# DC_DC_ISO.net
KiCad netlist of a schematic drawn in Altium Designer
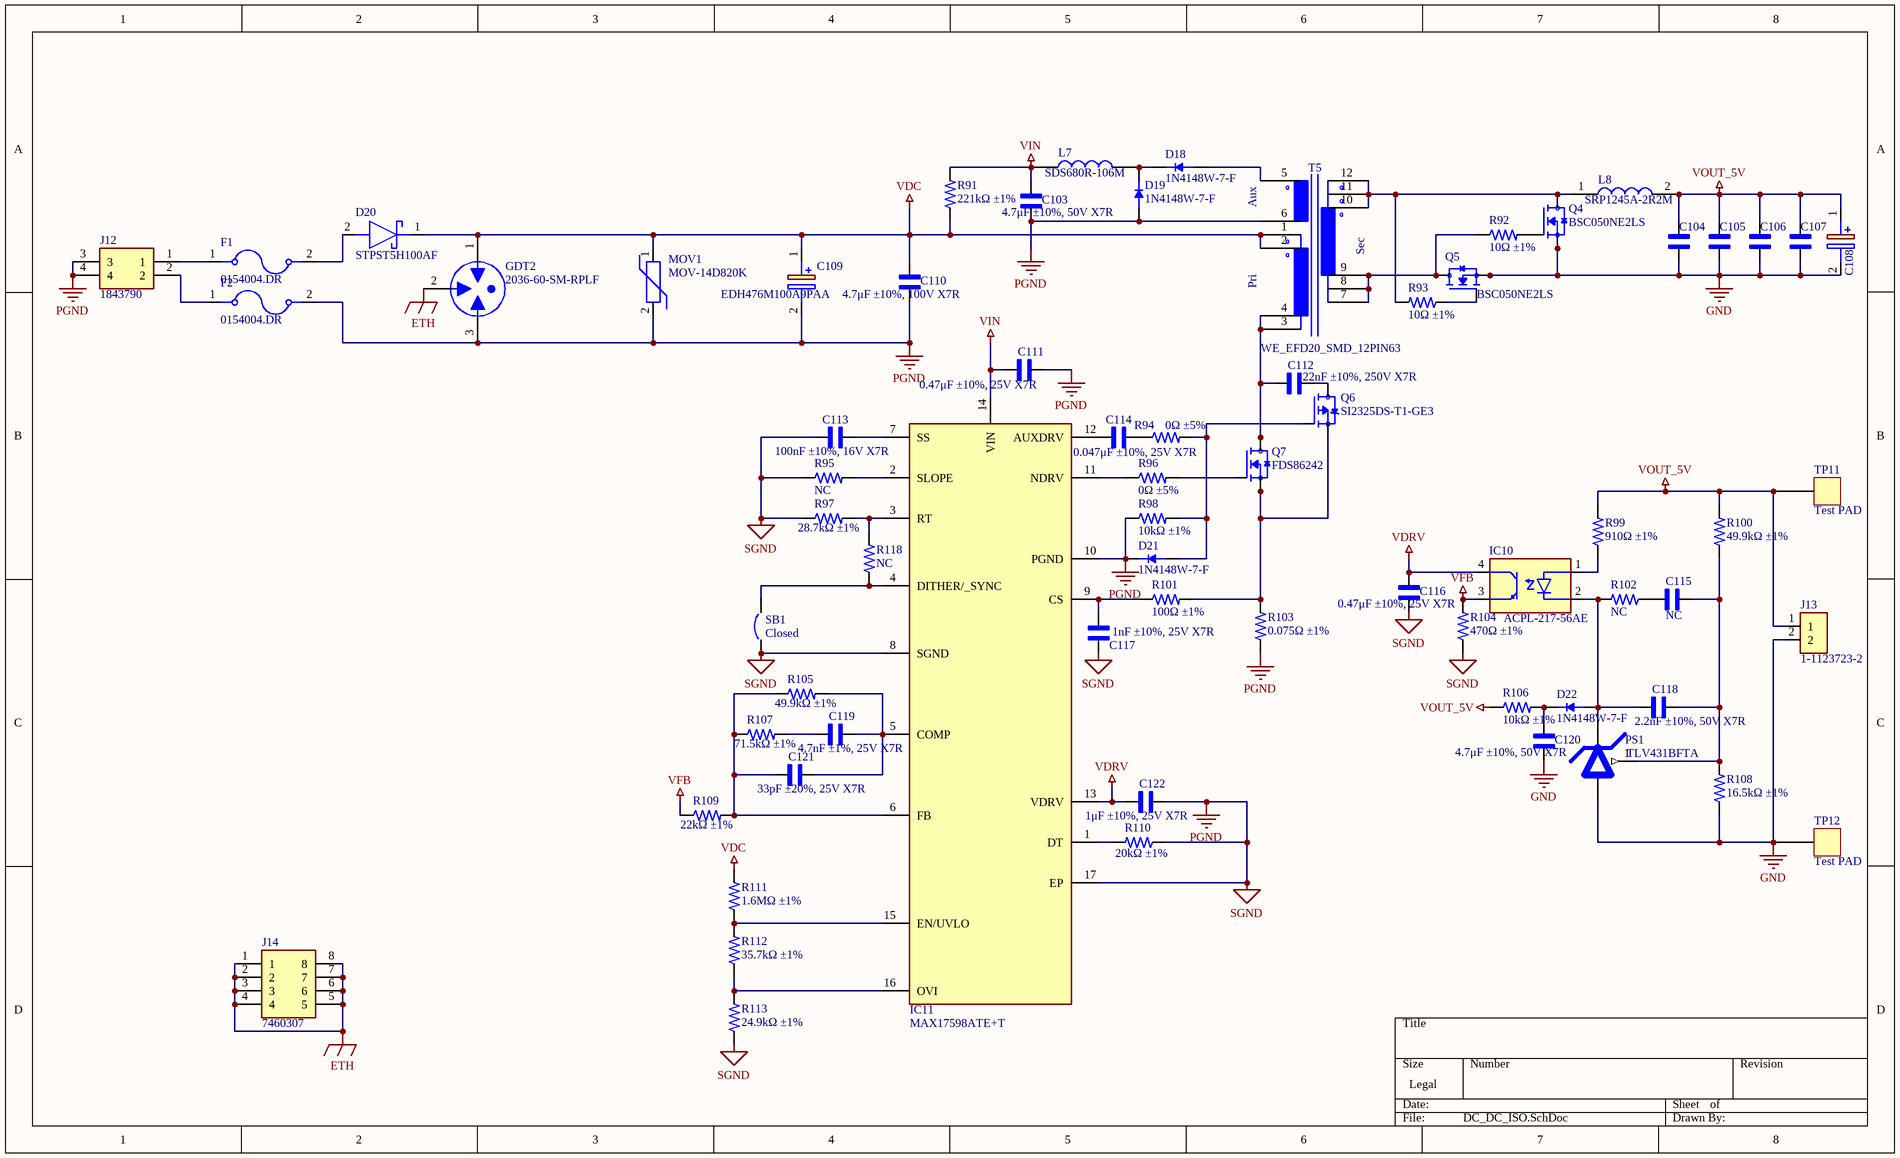
[diagram p0: DC_DC_ISO.SchDoc]

(export (version "E")
  (design (tool "Eeschema 10.0.6"))
  (components
    (comp (ref "C103")
      (value "4.7μF ±10%, 50V X7R")
      (footprint "1206_C")
      (fields (field (name "MP") "LD03ZD475MAB2A"))
      (libsource (lib "DC_DC") (part "CAP"))
    )
    (comp (ref "C104")
      (value "47μF ±10%, 10V X7R")
      (footprint "1210_C")
      (description "Capacitor non polar")
      (fields (field (name "MP") "LD03ZD475MAB2A"))
      (libsource (lib "DC_DC") (part "CAP"))
    )
    (comp (ref "C105")
      (value "47μF ±10%, 10V X7R")
      (footprint "1210_C")
      (description "Capacitor non polar")
      (fields (field (name "MP") "LD03ZD475MAB2A"))
      (libsource (lib "DC_DC") (part "CAP"))
    )
    (comp (ref "C106")
      (value "47μF ±10%, 10V X7R")
      (footprint "1210_C")
      (description "Capacitor non polar")
      (fields (field (name "MP") "LD03ZD475MAB2A"))
      (libsource (lib "DC_DC") (part "CAP"))
    )
    (comp (ref "C107")
      (value "47μF ±10%, 10V X7R")
      (footprint "1210_C")
      (description "Capacitor non polar")
      (fields (field (name "MP") "LD03ZD475MAB2A"))
      (libsource (lib "DC_DC") (part "CAP"))
    )
    (comp (ref "C108")
      (value "TCJ5477M016R0100E/NI")
      (footprint "SamacSys:CAPPM7344X400N")
      (description "Capacitor Polarised")
      (fields
        (field (name "MANUFACTURER_PART_NUMBER") "TCJ5477M016R0100E")
        (field (name "MOUSER PART NUMBER") "581-TCJ5477M016R100E")
      )
      (libsource (lib "*") (part "TCJ5477M016R0100E"))
    )
    (comp (ref "C109")
      (value "EDH476M100A9PAA")
      (footprint "SamacSys:CAPAE1030X1050N")
      (description "Capacitor Polarised")
      (fields (field (name "MOUSER PART NUMBER") "80-EDH476M100A9PAA"))
      (libsource (lib "*") (part "EDH476M100A9PAA"))
    )
    (comp (ref "C110")
      (value "4.7μF ±10%, 100V X7R")
      (footprint "1210_C")
      (fields (field (name "MP") "LD03ZD475MAB2A"))
      (libsource (lib "DC_DC") (part "CAP"))
    )
    (comp (ref "C111")
      (value "0.47μF ±10%, 25V X7R")
      (footprint "0603_C")
      (fields (field (name "MP") "LD03ZD475MAB2A"))
      (libsource (lib "") (part "CAP_1"))
    )
    (comp (ref "C112")
      (value "22nF ±10%, 250V X7R")
      (footprint "0805_C")
      (fields (field (name "MP") "LD03ZD475MAB2A"))
      (libsource (lib "") (part "CAP_2"))
    )
    (comp (ref "C113")
      (value "100nF ±10%, 16V X7R")
      (footprint "0603_C")
      (fields (field (name "MP") "LD03ZD475MAB2A"))
      (libsource (lib "") (part "CAP_1"))
    )
    (comp (ref "C114")
      (value "0.047μF ±10%, 25V X7R")
      (footprint "0603_C")
      (fields (field (name "MP") "LD03ZD475MAB2A"))
      (libsource (lib "") (part "CAP_2"))
    )
    (comp (ref "C115")
      (value "NC")
      (footprint "0603_C")
      (fields (field (name "MP") "LD03ZD475MAB2A"))
      (libsource (lib "") (part "CAP_2"))
    )
    (comp (ref "C116")
      (value "0.47μF ±10%, 25V X7R")
      (footprint "0603_C")
      (fields (field (name "MP") "LD03ZD475MAB2A"))
      (libsource (lib "DC_DC") (part "CAP"))
    )
    (comp (ref "C117")
      (value "1nF ±10%, 25V X7R")
      (footprint "0603_C")
      (fields (field (name "MP") "LD03ZD475MAB2A"))
      (libsource (lib "DC_DC") (part "CAP"))
    )
    (comp (ref "C118")
      (value "2.2nF ±10%, 50V X7R")
      (footprint "0603_C")
      (fields (field (name "MP") "LD03ZD475MAB2A"))
      (libsource (lib "") (part "CAP_2"))
    )
    (comp (ref "C119")
      (value "4.7nF ±1%, 25V X7R")
      (footprint "0603_C")
      (fields (field (name "MP") "LD03ZD475MAB2A"))
      (libsource (lib "") (part "CAP_1"))
    )
    (comp (ref "C120")
      (value "4.7μF ±10%, 50V X7R")
      (footprint "1206_C")
      (fields (field (name "MP") "LD03ZD475MAB2A"))
      (libsource (lib "DC_DC") (part "CAP"))
    )
    (comp (ref "C121")
      (value "33pF ±20%, 25V X7R")
      (footprint "0603_C")
      (fields (field (name "MP") "LD03ZD475MAB2A"))
      (libsource (lib "") (part "CAP_1"))
    )
    (comp (ref "C122")
      (value "1μF ±10%, 25V X7R")
      (footprint "0805_C")
      (fields (field (name "MP") "LD03ZD475MAB2A"))
      (libsource (lib "") (part "CAP_1"))
    )
    (comp (ref "D18")
      (value "1N4148W-7-F")
      (footprint "SOD3715X135N")
      (description "Diode Standard 100 V 300mA (DC) Surface Mount SOD-123")
      (fields (field (name "MF") "Diodes Inc."))
      (libsource (lib "DC_DC") (part "1N4148W-7-F"))
    )
    (comp (ref "D19")
      (value "1N4148W-7-F")
      (footprint "SOD3715X135N")
      (description "Diode Standard 100 V 300mA (DC) Surface Mount SOD-123")
      (fields (field (name "MF") "Diodes Inc."))
      (libsource (lib "DC_DC") (part "1N4148W-7-F"))
    )
    (comp (ref "D20")
      (value "STPST5H100AF")
      (footprint "SODFL4724X103N")
      (description "Schottky Diode")
      (fields (field (name "MOUSER PART NUMBER") "511-STPST5H100AF"))
      (libsource (lib "DC_DC") (part "STPST5H100AF"))
    )
    (comp (ref "D21")
      (value "1N4148W-7-F")
      (footprint "SOD3715X135N")
      (description "Diode Standard 100 V 300mA (DC) Surface Mount SOD-123")
      (fields (field (name "MF") "Diodes Inc."))
      (libsource (lib "DC_DC") (part "1N4148W-7-F"))
    )
    (comp (ref "D22")
      (value "1N4148W-7-F")
      (footprint "SOD3715X135N")
      (description "Diode Standard 100 V 300mA (DC) Surface Mount SOD-123")
      (fields (field (name "MF") "Diodes Inc."))
      (libsource (lib "DC_DC") (part "1N4148W-7-F"))
    )
    (comp (ref "F1")
      (value "0154004.DR")
      (footprint "FUSE_0154004.DR")
      (description "154/154T/154L/154TL Series OMNI-BLOKÂ® Fuse and Holder Assembly")
      (libsource (lib "DC_DC") (part "0154004.DR"))
    )
    (comp (ref "F2")
      (value "0154004.DR")
      (footprint "FUSE_0154004.DR")
      (description "154/154T/154L/154TL Series OMNI-BLOKÂ® Fuse and Holder Assembly")
      (libsource (lib "DC_DC") (part "0154004.DR"))
    )
    (comp (ref "GDT2")
      (value "2036-60-SM-RPLF")
      (footprint "2036-60-SM-RPLF")
      (description "Gas Discharge Tubes - GDTs / Gas Plasma Arrestors Sparkover100V/s 600V Miniature 3 Pole")
      (libsource (lib "DC_DC") (part "2036-60-SM-RPLF"))
    )
    (comp (ref "IC10")
      (value "ACPL-217-56AE")
      (footprint "SOIC127P700X242-4N")
      (description "Integrated Circuit")
      (fields (field (name "MOUSER PART NUMBER") "630-ACPL-217-56AE"))
      (libsource (lib "DC_DC") (part "ACPL-217-56AE"))
    )
    (comp (ref "IC11")
      (value "MAX17598ATE+T")
      (footprint "QFN50P300X300X80-17N")
      (description "Integrated Circuit")
      (fields (field (name "MOUSER PART NUMBER") "700-MAX17598ATE+T"))
      (libsource (lib "DC_DC") (part "MAX17598ATE+T"))
    )
    (comp (ref "J12")
      (value "1843790")
      (footprint "SamacSys:1843790")
      (description "Connector")
      (fields (field (name "MOUSER PART NUMBER") "651-1843790"))
      (libsource (lib "*") (part "1843790"))
    )
    (comp (ref "J13")
      (value "1-1123723-2")
      (footprint "TE_1-1123723-2")
      (description "3.96 EP HDR ASSY 2P_NATURAL_")
      (fields (field (name "MF") "TE Connectivity") (field (name "DIGI-KEY_PART_NUMBER") "A111830-ND"))
      (libsource (lib "1-1123723-2") (part "1-1123723-2"))
    )
    (comp (ref "J14")
      (value "7460307")
      (footprint "7460307")
      (description "Connector")
      (fields (field (name "MOUSER PART NUMBER") "710-7460307"))
      (libsource (lib "DC_DC") (part "7460307"))
    )
    (comp (ref "L7")
      (value "SDS680R-106M")
      (footprint "SRR6603332ML")
      (description "Inductor 10mH")
      (fields
        (field (name "MANUFACTURER_PART_NUMBER") "SRR6603-103ML")
        (field (name "MOUSER PART NUMBER") "652-SRR6603-103ML")
      )
      (libsource (lib "DC_DC") (part "SDS680R-106M"))
    )
    (comp (ref "L8")
      (value "SRP1245A-2R2M")
      (footprint "INDPM135125X500N")
      (description "Inductor 2.2uH")
      (fields (field (name "MOUSER PART NUMBER") "652-SRP1245A-2R2M"))
      (libsource (lib "DC_DC") (part "SRP1245A-2R2M"))
    )
    (comp (ref "MOV1")
      (value "MOV-14D820K")
      (footprint "MOV-14D820K")
      (description "Varistors 82volts 14mm")
      (fields (field (name "MP") "MOV-14D471K") (field (name "MF") "Bourns"))
      (libsource (lib "DC_DC") (part "MOV-14D820K"))
    )
    (comp (ref "PS1")
      (value "TLV431BFTA")
      (footprint "SOT96P240X100-3N")
      (description "Power Supply")
      (fields (field (name "MOUSER PART NUMBER") "621-TLV431BFTA"))
      (libsource (lib "DC_DC") (part "TLV431BFTA"))
    )
    (comp (ref "Q4")
      (value "BSC050NE2LS")
      (footprint "BSC050NE2LS")
      (description "MOSFET (N-Channel)")
      (fields (field (name "MOUSER PART NUMBER") "726-BSC050NE2LS"))
      (libsource (lib "DC_DC") (part "BSC050NE2LS"))
    )
    (comp (ref "Q5")
      (value "BSC050NE2LS")
      (footprint "BSC050NE2LS")
      (description "MOSFET (N-Channel)")
      (fields (field (name "MOUSER PART NUMBER") "726-BSC050NE2LS"))
      (libsource (lib "DC_DC") (part "BSC050NE2LS"))
    )
    (comp (ref "Q6")
      (value "SI2325DS-T1-GE3")
      (footprint "SOT-23")
      (description "150V 0.69A 1.25W 1.2ohm at 10V")
      (fields (field (name "MF") "Vishay Siliconix"))
      (libsource (lib "DC_DC") (part "SI2325DS-T1-GE3"))
    )
    (comp (ref "Q7")
      (value "FDS86242")
      (footprint "SOIC127P600X175-8N")
      (description "Integrated Circuit")
      (fields (field (name "MOUSER PART NUMBER") "512-FDS86242"))
      (libsource (lib "DC_DC") (part "FDS86242"))
    )
    (comp (ref "R91")
      (value "221kΩ ±1%")
      (footprint "0805_R")
      (fields (field (name "MP") "3-1879460-6"))
      (libsource (lib "DC_DC") (part "RES"))
    )
    (comp (ref "R92")
      (value "10Ω ±1%")
      (footprint "0603_R")
      (fields (field (name "MP") "3-1879460-6"))
      (libsource (lib "DC_DC") (part "RES"))
    )
    (comp (ref "R93")
      (value "10Ω ±1%")
      (footprint "0603_R")
      (fields (field (name "MP") "3-1879460-6"))
      (libsource (lib "DC_DC") (part "RES"))
    )
    (comp (ref "R94")
      (value "0Ω ±5%")
      (footprint "0603_R")
      (fields (field (name "MP") "3-1879460-6"))
      (libsource (lib "DC_DC") (part "RES"))
    )
    (comp (ref "R95")
      (value "NC")
      (footprint "0603_R")
      (fields (field (name "MP") "3-1879460-6"))
      (libsource (lib "DC_DC") (part "RES"))
    )
    (comp (ref "R96")
      (value "0Ω ±5%")
      (footprint "0603_R")
      (fields (field (name "MP") "3-1879460-6"))
      (libsource (lib "DC_DC") (part "RES"))
    )
    (comp (ref "R97")
      (value "28.7kΩ ±1%")
      (footprint "0603_R")
      (fields (field (name "MP") "3-1879460-6"))
      (libsource (lib "DC_DC") (part "RES"))
    )
    (comp (ref "R98")
      (value "10kΩ ±1%")
      (footprint "0603_R")
      (fields (field (name "MP") "3-1879460-6"))
      (libsource (lib "DC_DC") (part "RES"))
    )
    (comp (ref "R99")
      (value "910Ω ±1%")
      (footprint "0603_R")
      (fields (field (name "MP") "3-1879460-6"))
      (libsource (lib "DC_DC") (part "RES"))
    )
    (comp (ref "R100")
      (value "49.9kΩ ±1%")
      (footprint "0603_R")
      (fields (field (name "MP") "3-1879460-6"))
      (libsource (lib "DC_DC") (part "RES"))
    )
    (comp (ref "R101")
      (value "100Ω ±1%")
      (footprint "0603_R")
      (fields (field (name "MP") "3-1879460-6"))
      (libsource (lib "DC_DC") (part "RES"))
    )
    (comp (ref "R102")
      (value "NC")
      (footprint "0603_R")
      (fields (field (name "MP") "3-1879460-6"))
      (libsource (lib "DC_DC") (part "RES"))
    )
    (comp (ref "R103")
      (value "0.075Ω ±1%")
      (footprint "1206_R")
      (fields (field (name "MP") "3-1879460-6"))
      (libsource (lib "DC_DC") (part "RES"))
    )
    (comp (ref "R104")
      (value "470Ω ±1%")
      (footprint "0603_R")
      (fields (field (name "MP") "3-1879460-6"))
      (libsource (lib "DC_DC") (part "RES"))
    )
    (comp (ref "R105")
      (value "49.9kΩ ±1%")
      (footprint "0603_R")
      (fields (field (name "MP") "3-1879460-6"))
      (libsource (lib "DC_DC") (part "RES"))
    )
    (comp (ref "R106")
      (value "10kΩ ±1%")
      (footprint "0603_R")
      (fields (field (name "MP") "3-1879460-6"))
      (libsource (lib "DC_DC") (part "RES"))
    )
    (comp (ref "R107")
      (value "71.5kΩ ±1%")
      (footprint "0603_R")
      (fields (field (name "MP") "3-1879460-6"))
      (libsource (lib "DC_DC") (part "RES"))
    )
    (comp (ref "R108")
      (value "16.5kΩ ±1%")
      (footprint "0603_R")
      (fields (field (name "MP") "3-1879460-6"))
      (libsource (lib "DC_DC") (part "RES"))
    )
    (comp (ref "R109")
      (value "22kΩ ±1%")
      (footprint "0603_R")
      (fields (field (name "MP") "3-1879460-6"))
      (libsource (lib "DC_DC") (part "RES"))
    )
    (comp (ref "R110")
      (value "20kΩ ±1%")
      (footprint "0603_R")
      (fields (field (name "MP") "3-1879460-6"))
      (libsource (lib "DC_DC") (part "RES"))
    )
    (comp (ref "R111")
      (value "1.6MΩ ±1%")
      (footprint "0805_R")
      (fields (field (name "MP") "3-1879460-6"))
      (libsource (lib "DC_DC") (part "RES"))
    )
    (comp (ref "R112")
      (value "35.7kΩ ±1%")
      (footprint "0603_R")
      (fields (field (name "MP") "3-1879460-6"))
      (libsource (lib "DC_DC") (part "RES"))
    )
    (comp (ref "R113")
      (value "24.9kΩ ±1%")
      (footprint "0603_R")
      (fields (field (name "MP") "3-1879460-6"))
      (libsource (lib "DC_DC") (part "RES"))
    )
    (comp (ref "R118")
      (value "NC")
      (footprint "0603_R")
      (fields (field (name "MP") "3-1879460-6"))
      (libsource (lib "IIOT_GATEWAY_MT7621") (part "RES"))
    )
    (comp (ref "SB1")
      (value "Closed")
      (footprint "SB_0603")
      (description "Circuit Breaker")
      (fields (field (name "PUBLISHER") "Altium Limited"))
      (libsource (lib "BV100011_UniversalSlave") (part "Circuit Breaker_close"))
    )
    (comp (ref "T5")
      (value "WE_EFD20_SMD_12PIN63")
      (footprint "WE_EFD20_SMD_12PIN63")
      (description "Transformer")
      (fields
        (field (name "MANUFACTURER_PART_NUMBER") "7491194912")
        (field (name "MOUSER PART NUMBER") "710-7491194912")
      )
      (libsource (lib "DC_DC") (part "WE_EFD20_SMD_12PIN63"))
    )
    (comp (ref "TP11") (value "Test PAD") (footprint "Test PAD") (libsource (lib "DC_DC") (part "Test PAD")))
    (comp (ref "TP12") (value "Test PAD") (footprint "Test PAD") (libsource (lib "DC_DC") (part "Test PAD")))
  )
  (nets
    (net (code "1") (name "ETH") (class "Default")
      (node (ref "GDT2") (pin "2") (pinfunction "E_2") (pintype "passive"))
      (node (ref "J14") (pin "1") (pinfunction "1_1") (pintype "passive"))
      (node (ref "J14") (pin "2") (pinfunction "2_2") (pintype "passive"))
      (node (ref "J14") (pin "3") (pinfunction "3_3") (pintype "passive"))
      (node (ref "J14") (pin "4") (pinfunction "4_4") (pintype "passive"))
      (node (ref "J14") (pin "5") (pinfunction "5_5") (pintype "passive"))
      (node (ref "J14") (pin "6") (pinfunction "6_6") (pintype "passive"))
      (node (ref "J14") (pin "7") (pinfunction "7_7") (pintype "passive"))
      (node (ref "J14") (pin "8") (pinfunction "8_8") (pintype "passive"))
    )
    (net (code "2") (name "GND") (class "Default")
      (node (ref "C104") (pin "2") (pinfunction "2_2") (pintype "passive"))
      (node (ref "C105") (pin "2") (pinfunction "2_2") (pintype "passive"))
      (node (ref "C106") (pin "2") (pinfunction "2_2") (pintype "passive"))
      (node (ref "C107") (pin "2") (pinfunction "2_2") (pintype "passive"))
      (node (ref "C108") (pin "2") (pinfunction "-_2") (pintype "passive"))
      (node (ref "C120") (pin "2") (pinfunction "2_2") (pintype "passive"))
      (node (ref "J13") (pin "2") (pinfunction "2_2") (pintype "passive"))
      (node (ref "PS1") (pin "3") (pinfunction "ANODE_3") (pintype "power_in"))
      (node (ref "Q4") (pin "1") (pinfunction "S_1") (pintype "passive"))
      (node (ref "Q4") (pin "2") (pinfunction "S_2") (pintype "passive"))
      (node (ref "Q4") (pin "3") (pinfunction "S_3") (pintype "passive"))
      (node (ref "Q5") (pin "1") (pinfunction "S_1") (pintype "passive"))
      (node (ref "Q5") (pin "2") (pinfunction "S_2") (pintype "passive"))
      (node (ref "Q5") (pin "3") (pinfunction "S_3") (pintype "passive"))
      (node (ref "R108") (pin "1") (pinfunction "1_1") (pintype "passive"))
      (node (ref "TP12") (pin "1") (pinfunction "1_1") (pintype "passive"))
    )
    (net (code "3") (name "Net-(C112-Pad2)") (class "Default")
      (node (ref "C112") (pin "2") (pinfunction "2_2") (pintype "passive"))
      (node (ref "Q7") (pin "5") (pinfunction "D_5") (pintype "passive"))
      (node (ref "Q7") (pin "6") (pinfunction "D_6") (pintype "passive"))
      (node (ref "Q7") (pin "7") (pinfunction "D_7") (pintype "passive"))
      (node (ref "Q7") (pin "8") (pinfunction "D_8") (pintype "passive"))
      (node (ref "T5") (pin "3") (pinfunction "3_3") (pintype "passive"))
      (node (ref "T5") (pin "4") (pinfunction "4_4") (pintype "passive"))
    )
    (net (code "4") (name "Net-(C114-Pad1)") (class "Default")
      (node (ref "C114") (pin "1") (pinfunction "1_1") (pintype "passive"))
      (node (ref "R94") (pin "1") (pinfunction "1_1") (pintype "passive"))
    )
    (net (code "5") (name "Net-(C115-Pad2)") (class "Default")
      (node (ref "C115") (pin "2") (pinfunction "2_2") (pintype "passive"))
      (node (ref "R102") (pin "1") (pinfunction "1_1") (pintype "passive"))
    )
    (net (code "6") (name "Net-(C119-Pad1)") (class "Default")
      (node (ref "C119") (pin "1") (pinfunction "1_1") (pintype "passive"))
      (node (ref "R107") (pin "2") (pinfunction "2_2") (pintype "passive"))
    )
    (net (code "7") (name "Net-(D18-K)") (class "Default")
      (node (ref "D18") (pin "C") (pinfunction "K_C") (pintype "passive"))
      (node (ref "D19") (pin "C") (pinfunction "K_C") (pintype "passive"))
      (node (ref "L7") (pin "2") (pinfunction "2_2") (pintype "passive"))
    )
    (net (code "8") (name "Net-(D18-PadA)") (class "Default")
      (node (ref "D18") (pin "A") (pinfunction "A_A") (pintype "passive"))
      (node (ref "T5") (pin "5") (pinfunction "5_5") (pintype "passive"))
    )
    (net (code "9") (name "Net-(D20-A)") (class "Default")
      (node (ref "D20") (pin "2") (pinfunction "A_2") (pintype "passive"))
      (node (ref "F1") (pin "2") (pinfunction "2_2") (pintype "passive"))
    )
    (net (code "10") (name "Net-(D22-K)") (class "Default")
      (node (ref "C120") (pin "1") (pinfunction "1_1") (pintype "passive"))
      (node (ref "D22") (pin "C") (pinfunction "K_C") (pintype "passive"))
      (node (ref "R106") (pin "2") (pinfunction "2_2") (pintype "passive"))
    )
    (net (code "11") (name "Net-(F1-Pad1)") (class "Default")
      (node (ref "F1") (pin "1") (pinfunction "1_1") (pintype "passive"))
      (node (ref "J12") (pin "1") (pinfunction "1_1") (pintype "passive"))
    )
    (net (code "12") (name "Net-(F2-Pad1)") (class "Default")
      (node (ref "F2") (pin "1") (pinfunction "1_1") (pintype "passive"))
      (node (ref "J12") (pin "2") (pinfunction "2_2") (pintype "passive"))
    )
    (net (code "13") (name "Net-(IC10-ANODE)") (class "Default")
      (node (ref "IC10") (pin "1") (pinfunction "ANODE_1") (pintype "passive"))
      (node (ref "R99") (pin "1") (pinfunction "1_1") (pintype "passive"))
    )
    (net (code "14") (name "Net-(IC10-CATHODE)") (class "Default")
      (node (ref "C118") (pin "2") (pinfunction "2_2") (pintype "passive"))
      (node (ref "D22") (pin "A") (pinfunction "A_A") (pintype "passive"))
      (node (ref "IC10") (pin "2") (pinfunction "CATHODE_2") (pintype "passive"))
      (node (ref "PS1") (pin "2") (pinfunction "CATHODE_2") (pintype "power_in"))
      (node (ref "R102") (pin "2") (pinfunction "2_2") (pintype "passive"))
    )
    (net (code "15") (name "Net-(IC11-AUXDRV)") (class "Default")
      (node (ref "C114") (pin "2") (pinfunction "2_2") (pintype "passive"))
      (node (ref "IC11") (pin "12") (pinfunction "AUXDRV_12") (pintype "passive"))
    )
    (net (code "16") (name "Net-(IC11-COMP)") (class "Default")
      (node (ref "C119") (pin "2") (pinfunction "2_2") (pintype "passive"))
      (node (ref "C121") (pin "2") (pinfunction "2_2") (pintype "passive"))
      (node (ref "IC11") (pin "5") (pinfunction "COMP_5") (pintype "passive"))
      (node (ref "R105") (pin "2") (pinfunction "2_2") (pintype "passive"))
    )
    (net (code "17") (name "Net-(IC11-CS)") (class "Default")
      (node (ref "C117") (pin "1") (pinfunction "1_1") (pintype "passive"))
      (node (ref "IC11") (pin "9") (pinfunction "CS_9") (pintype "passive"))
      (node (ref "R101") (pin "1") (pinfunction "1_1") (pintype "passive"))
    )
    (net (code "18") (name "Net-(IC11-DITHER{slash}_SYNC)") (class "Default")
      (node (ref "IC11") (pin "4") (pinfunction "DITHER/_SYNC_4") (pintype "passive"))
      (node (ref "R118") (pin "1") (pinfunction "1_1") (pintype "passive"))
      (node (ref "SB1") (pin "2") (pinfunction "2_2") (pintype "passive"))
    )
    (net (code "19") (name "Net-(IC11-DT)") (class "Default")
      (node (ref "IC11") (pin "1") (pinfunction "DT_1") (pintype "passive"))
      (node (ref "R110") (pin "2") (pinfunction "2_2") (pintype "passive"))
    )
    (net (code "20") (name "Net-(IC11-EN{slash}UVLO)") (class "Default")
      (node (ref "IC11") (pin "15") (pinfunction "EN/UVLO_15") (pintype "passive"))
      (node (ref "R111") (pin "1") (pinfunction "1_1") (pintype "passive"))
      (node (ref "R112") (pin "2") (pinfunction "2_2") (pintype "passive"))
    )
    (net (code "21") (name "Net-(IC11-FB)") (class "Default")
      (node (ref "C121") (pin "1") (pinfunction "1_1") (pintype "passive"))
      (node (ref "IC11") (pin "6") (pinfunction "FB_6") (pintype "passive"))
      (node (ref "R105") (pin "1") (pinfunction "1_1") (pintype "passive"))
      (node (ref "R107") (pin "1") (pinfunction "1_1") (pintype "passive"))
      (node (ref "R109") (pin "2") (pinfunction "2_2") (pintype "passive"))
    )
    (net (code "22") (name "Net-(IC11-NDRV)") (class "Default")
      (node (ref "IC11") (pin "11") (pinfunction "NDRV_11") (pintype "passive"))
      (node (ref "R96") (pin "1") (pinfunction "1_1") (pintype "passive"))
    )
    (net (code "23") (name "Net-(IC11-OVI)") (class "Default")
      (node (ref "IC11") (pin "16") (pinfunction "OVI_16") (pintype "passive"))
      (node (ref "R112") (pin "1") (pinfunction "1_1") (pintype "passive"))
      (node (ref "R113") (pin "2") (pinfunction "2_2") (pintype "passive"))
    )
    (net (code "24") (name "Net-(IC11-RT)") (class "Default")
      (node (ref "IC11") (pin "3") (pinfunction "RT_3") (pintype "passive"))
      (node (ref "R118") (pin "2") (pinfunction "2_2") (pintype "passive"))
      (node (ref "R97") (pin "2") (pinfunction "2_2") (pintype "passive"))
    )
    (net (code "25") (name "Net-(IC11-SLOPE)") (class "Default")
      (node (ref "IC11") (pin "2") (pinfunction "SLOPE_2") (pintype "passive"))
      (node (ref "R95") (pin "2") (pinfunction "2_2") (pintype "passive"))
    )
    (net (code "26") (name "Net-(IC11-SS)") (class "Default")
      (node (ref "C113") (pin "2") (pinfunction "2_2") (pintype "passive"))
      (node (ref "IC11") (pin "7") (pinfunction "SS_7") (pintype "passive"))
    )
    (net (code "27") (name "Net-(L8-Pad1)") (class "Default")
      (node (ref "L8") (pin "1") (pinfunction "1_1") (pintype "passive"))
      (node (ref "Q4") (pin "5") (pinfunction "D_5") (pintype "passive"))
      (node (ref "Q4") (pin "6") (pinfunction "D_6") (pintype "passive"))
      (node (ref "Q4") (pin "7") (pinfunction "D_7") (pintype "passive"))
      (node (ref "Q4") (pin "8") (pinfunction "D_8") (pintype "passive"))
      (node (ref "Q4") (pin "9") (pinfunction "D_9") (pintype "passive"))
      (node (ref "R93") (pin "2") (pinfunction "2_2") (pintype "passive"))
      (node (ref "T5") (pin "10") (pinfunction "10_10") (pintype "passive"))
      (node (ref "T5") (pin "11") (pinfunction "11_11") (pintype "passive"))
      (node (ref "T5") (pin "12") (pinfunction "12_12") (pintype "passive"))
    )
    (net (code "28") (name "Net-(PS1-REF)") (class "Default")
      (node (ref "C115") (pin "1") (pinfunction "1_1") (pintype "passive"))
      (node (ref "C118") (pin "1") (pinfunction "1_1") (pintype "passive"))
      (node (ref "PS1") (pin "1") (pinfunction "REF_1") (pintype "output"))
      (node (ref "R100") (pin "1") (pinfunction "1_1") (pintype "passive"))
      (node (ref "R108") (pin "2") (pinfunction "2_2") (pintype "passive"))
    )
    (net (code "29") (name "Net-(Q4-G)") (class "Default")
      (node (ref "Q4") (pin "4") (pinfunction "G_4") (pintype "passive"))
      (node (ref "R92") (pin "2") (pinfunction "2_2") (pintype "passive"))
    )
    (net (code "30") (name "Net-(Q5-D-Pad5)") (class "Default")
      (node (ref "Q5") (pin "5") (pinfunction "D_5") (pintype "passive"))
      (node (ref "Q5") (pin "6") (pinfunction "D_6") (pintype "passive"))
      (node (ref "Q5") (pin "7") (pinfunction "D_7") (pintype "passive"))
      (node (ref "Q5") (pin "8") (pinfunction "D_8") (pintype "passive"))
      (node (ref "Q5") (pin "9") (pinfunction "D_9") (pintype "passive"))
      (node (ref "R92") (pin "1") (pinfunction "1_1") (pintype "passive"))
      (node (ref "T5") (pin "7") (pinfunction "7_7") (pintype "passive"))
      (node (ref "T5") (pin "8") (pinfunction "8_8") (pintype "passive"))
      (node (ref "T5") (pin "9") (pinfunction "9_9") (pintype "passive"))
    )
    (net (code "31") (name "Net-(Q5-G)") (class "Default")
      (node (ref "Q5") (pin "4") (pinfunction "G_4") (pintype "passive"))
      (node (ref "R93") (pin "1") (pinfunction "1_1") (pintype "passive"))
    )
    (net (code "32") (name "Net-(Q6-D)") (class "Default")
      (node (ref "C112") (pin "1") (pinfunction "1_1") (pintype "passive"))
      (node (ref "Q6") (pin "3") (pinfunction "D_3") (pintype "passive"))
    )
    (net (code "33") (name "Net-(Q6-G)") (class "Default")
      (node (ref "D21") (pin "A") (pinfunction "A_A") (pintype "passive"))
      (node (ref "Q6") (pin "1") (pinfunction "G_1") (pintype "passive"))
      (node (ref "R94") (pin "2") (pinfunction "2_2") (pintype "passive"))
      (node (ref "R98") (pin "2") (pinfunction "2_2") (pintype "passive"))
    )
    (net (code "34") (name "Net-(Q6-S)") (class "Default")
      (node (ref "Q6") (pin "2") (pinfunction "S_2") (pintype "passive"))
      (node (ref "Q7") (pin "1") (pinfunction "S_1") (pintype "passive"))
      (node (ref "Q7") (pin "2") (pinfunction "S_2") (pintype "passive"))
      (node (ref "Q7") (pin "3") (pinfunction "S_3") (pintype "passive"))
      (node (ref "R101") (pin "2") (pinfunction "2_2") (pintype "passive"))
      (node (ref "R103") (pin "2") (pinfunction "2_2") (pintype "passive"))
    )
    (net (code "35") (name "Net-(Q7-G)") (class "Default")
      (node (ref "Q7") (pin "4") (pinfunction "G_4") (pintype "passive"))
      (node (ref "R96") (pin "2") (pinfunction "2_2") (pintype "passive"))
    )
    (net (code "36") (name "PGND") (class "Default")
      (node (ref "C103") (pin "2") (pinfunction "2_2") (pintype "passive"))
      (node (ref "C109") (pin "2") (pinfunction "-_2") (pintype "passive"))
      (node (ref "C110") (pin "2") (pinfunction "2_2") (pintype "passive"))
      (node (ref "C111") (pin "2") (pinfunction "2_2") (pintype "passive"))
      (node (ref "C113") (pin "1") (pinfunction "1_1") (pintype "passive"))
      (node (ref "C116") (pin "2") (pinfunction "2_2") (pintype "passive"))
      (node (ref "C117") (pin "2") (pinfunction "2_2") (pintype "passive"))
      (node (ref "C122") (pin "2") (pinfunction "2_2") (pintype "passive"))
      (node (ref "D19") (pin "A") (pinfunction "A_A") (pintype "passive"))
      (node (ref "D21") (pin "C") (pinfunction "K_C") (pintype "passive"))
      (node (ref "F2") (pin "2") (pinfunction "2_2") (pintype "passive"))
      (node (ref "GDT2") (pin "3") (pinfunction "B_3") (pintype "passive"))
      (node (ref "IC11") (pin "10") (pinfunction "PGND_10") (pintype "passive"))
      (node (ref "IC11") (pin "17") (pinfunction "EP_17") (pintype "passive"))
      (node (ref "IC11") (pin "8") (pinfunction "SGND_8") (pintype "passive"))
      (node (ref "J12") (pin "3") (pinfunction "3_3") (pintype "passive"))
      (node (ref "J12") (pin "4") (pinfunction "4_4") (pintype "passive"))
      (node (ref "MOV1") (pin "2") (pinfunction "2_2") (pintype "bidirectional"))
      (node (ref "R103") (pin "1") (pinfunction "1_1") (pintype "passive"))
      (node (ref "R104") (pin "1") (pinfunction "1_1") (pintype "passive"))
      (node (ref "R110") (pin "1") (pinfunction "1_1") (pintype "passive"))
      (node (ref "R113") (pin "1") (pinfunction "1_1") (pintype "passive"))
      (node (ref "R95") (pin "1") (pinfunction "1_1") (pintype "passive"))
      (node (ref "R97") (pin "1") (pinfunction "1_1") (pintype "passive"))
      (node (ref "R98") (pin "1") (pinfunction "1_1") (pintype "passive"))
      (node (ref "SB1") (pin "1") (pinfunction "1_1") (pintype "passive"))
      (node (ref "T5") (pin "6") (pinfunction "6_6") (pintype "passive"))
    )
    (net (code "37") (name "VDC") (class "Default")
      (node (ref "C109") (pin "1") (pinfunction "+_1") (pintype "passive"))
      (node (ref "C110") (pin "1") (pinfunction "1_1") (pintype "passive"))
      (node (ref "D20") (pin "1") (pinfunction "K_1") (pintype "passive"))
      (node (ref "GDT2") (pin "1") (pinfunction "A_1") (pintype "passive"))
      (node (ref "MOV1") (pin "1") (pinfunction "1_1") (pintype "bidirectional"))
      (node (ref "R111") (pin "2") (pinfunction "2_2") (pintype "passive"))
      (node (ref "R91") (pin "1") (pinfunction "1_1") (pintype "passive"))
      (node (ref "T5") (pin "1") (pinfunction "1_1") (pintype "passive"))
      (node (ref "T5") (pin "2") (pinfunction "2_2") (pintype "passive"))
    )
    (net (code "38") (name "VDRV") (class "Default")
      (node (ref "C116") (pin "1") (pinfunction "1_1") (pintype "passive"))
      (node (ref "C122") (pin "1") (pinfunction "1_1") (pintype "passive"))
      (node (ref "IC10") (pin "4") (pinfunction "COLLECTOR_4") (pintype "passive"))
      (node (ref "IC11") (pin "13") (pinfunction "VDRV_13") (pintype "passive"))
    )
    (net (code "39") (name "VFB") (class "Default")
      (node (ref "IC10") (pin "3") (pinfunction "EMITTER_3") (pintype "passive"))
      (node (ref "R104") (pin "2") (pinfunction "2_2") (pintype "passive"))
      (node (ref "R109") (pin "1") (pinfunction "1_1") (pintype "passive"))
    )
    (net (code "40") (name "VIN") (class "Default")
      (node (ref "C103") (pin "1") (pinfunction "1_1") (pintype "passive"))
      (node (ref "C111") (pin "1") (pinfunction "1_1") (pintype "passive"))
      (node (ref "IC11") (pin "14") (pinfunction "VIN_14") (pintype "passive"))
      (node (ref "L7") (pin "1") (pinfunction "1_1") (pintype "passive"))
      (node (ref "R91") (pin "2") (pinfunction "2_2") (pintype "passive"))
    )
    (net (code "41") (name "VOUT_5V") (class "Default")
      (node (ref "C104") (pin "1") (pinfunction "1_1") (pintype "passive"))
      (node (ref "C105") (pin "1") (pinfunction "1_1") (pintype "passive"))
      (node (ref "C106") (pin "1") (pinfunction "1_1") (pintype "passive"))
      (node (ref "C107") (pin "1") (pinfunction "1_1") (pintype "passive"))
      (node (ref "C108") (pin "1") (pinfunction "+_1") (pintype "passive"))
      (node (ref "J13") (pin "1") (pinfunction "1_1") (pintype "passive"))
      (node (ref "L8") (pin "2") (pinfunction "2_2") (pintype "passive"))
      (node (ref "R100") (pin "2") (pinfunction "2_2") (pintype "passive"))
      (node (ref "R106") (pin "1") (pinfunction "1_1") (pintype "passive"))
      (node (ref "R99") (pin "2") (pinfunction "2_2") (pintype "passive"))
      (node (ref "TP11") (pin "1") (pinfunction "1_1") (pintype "passive"))
    )
  )
)
